# tenere-controller-rev-B.net
KiCad netlist of a schematic drawn in EAGLE
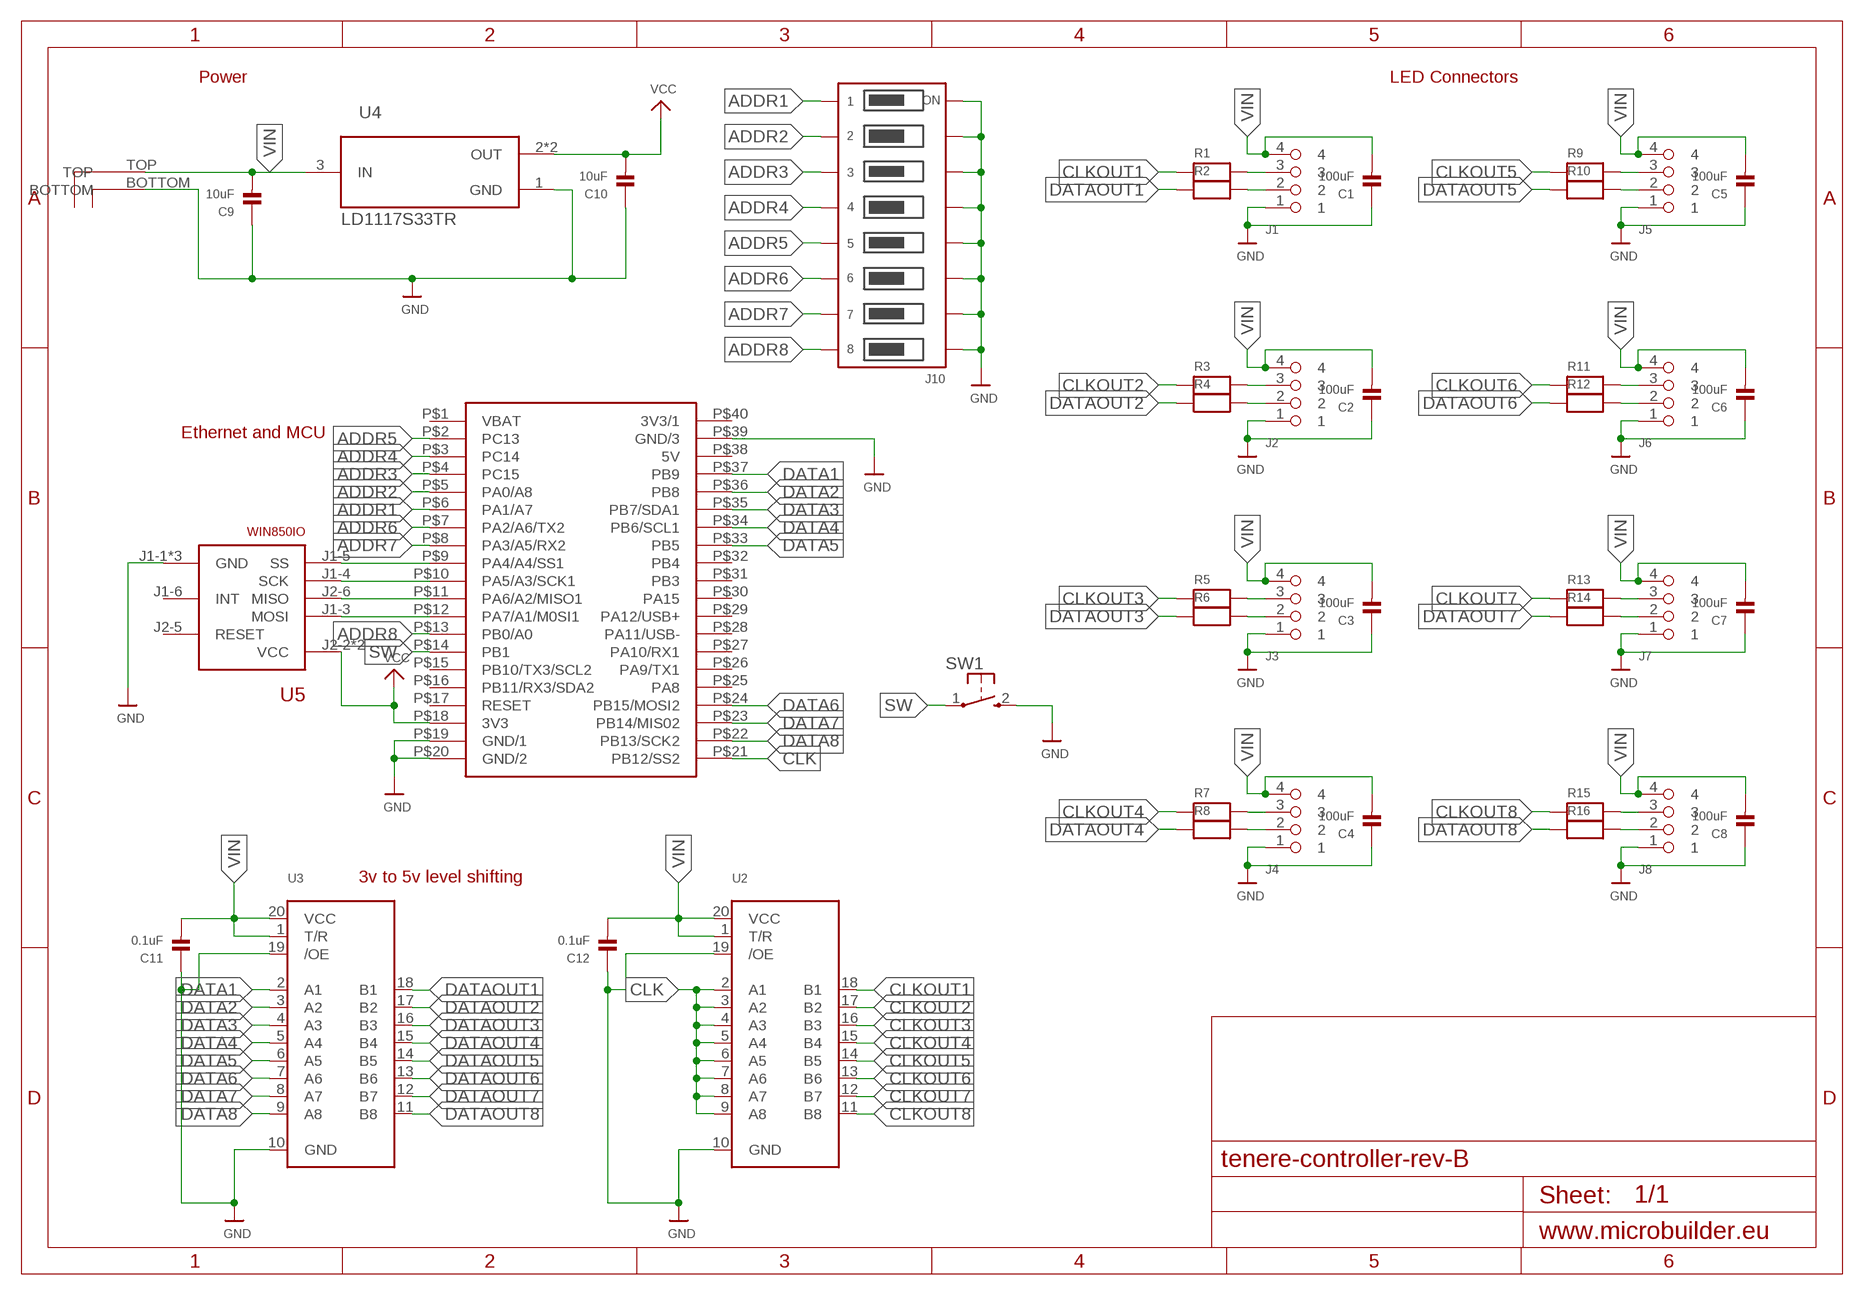
[diagram p0: schematic, sheet 1]

(export (version "E")
  (design (tool "Eeschema 10.0.6"))
  (components
    (comp (ref "C1")
      (value "100uF")
      (footprint "eagle-import:1206")
      (libsource (lib "eagle-import") (part "CAP_CERAMIC1206"))
    )
    (comp (ref "C2")
      (value "100uF")
      (footprint "eagle-import:1206")
      (libsource (lib "eagle-import") (part "CAP_CERAMIC1206"))
    )
    (comp (ref "C3")
      (value "100uF")
      (footprint "eagle-import:1206")
      (libsource (lib "eagle-import") (part "CAP_CERAMIC1206"))
    )
    (comp (ref "C4")
      (value "100uF")
      (footprint "eagle-import:1206")
      (libsource (lib "eagle-import") (part "CAP_CERAMIC1206"))
    )
    (comp (ref "C5")
      (value "100uF")
      (footprint "eagle-import:1206")
      (libsource (lib "eagle-import") (part "CAP_CERAMIC1206"))
    )
    (comp (ref "C6")
      (value "100uF")
      (footprint "eagle-import:1206")
      (libsource (lib "eagle-import") (part "CAP_CERAMIC1206"))
    )
    (comp (ref "C7")
      (value "100uF")
      (footprint "eagle-import:1206")
      (libsource (lib "eagle-import") (part "CAP_CERAMIC1206"))
    )
    (comp (ref "C8")
      (value "100uF")
      (footprint "eagle-import:1206")
      (libsource (lib "eagle-import") (part "CAP_CERAMIC1206"))
    )
    (comp (ref "C9")
      (value "10uF")
      (footprint "eagle-import:0603")
      (libsource (lib "eagle-import") (part "CAP_CERAMIC0603"))
    )
    (comp (ref "C10")
      (value "10uF")
      (footprint "eagle-import:0603")
      (libsource (lib "eagle-import") (part "CAP_CERAMIC0603"))
    )
    (comp (ref "C11")
      (value "0.1uF")
      (footprint "eagle-import:0603")
      (libsource (lib "eagle-import") (part "CAP_CERAMIC0603"))
    )
    (comp (ref "C12")
      (value "0.1uF")
      (footprint "eagle-import:0603")
      (libsource (lib "eagle-import") (part "CAP_CERAMIC0603"))
    )
    (comp (ref "J1")
      (value "MICROFIT3")
      (footprint "eagle-import:43650-0400")
      (libsource (lib "eagle-import") (part "MICROFIT3"))
    )
    (comp (ref "J2")
      (value "MICROFIT3")
      (footprint "eagle-import:43650-0400")
      (libsource (lib "eagle-import") (part "MICROFIT3"))
    )
    (comp (ref "J3")
      (value "MICROFIT3")
      (footprint "eagle-import:43650-0400")
      (libsource (lib "eagle-import") (part "MICROFIT3"))
    )
    (comp (ref "J4")
      (value "MICROFIT3")
      (footprint "eagle-import:43650-0400")
      (libsource (lib "eagle-import") (part "MICROFIT3"))
    )
    (comp (ref "J5")
      (value "MICROFIT3")
      (footprint "eagle-import:43650-0400")
      (libsource (lib "eagle-import") (part "MICROFIT3"))
    )
    (comp (ref "J6")
      (value "MICROFIT3")
      (footprint "eagle-import:43650-0400")
      (libsource (lib "eagle-import") (part "MICROFIT3"))
    )
    (comp (ref "J7")
      (value "MICROFIT3")
      (footprint "eagle-import:43650-0400")
      (libsource (lib "eagle-import") (part "MICROFIT3"))
    )
    (comp (ref "J8")
      (value "MICROFIT3")
      (footprint "eagle-import:43650-0400")
      (libsource (lib "eagle-import") (part "MICROFIT3"))
    )
    (comp (ref "J10")
      (value "DIP-SWITCH-8PIN")
      (footprint "eagle-import:BPA08B")
      (libsource (lib "eagle-import") (part "DIP-SWITCH-8PIN"))
    )
    (comp (ref "PWR")
      (value "POWERPOLE-2V")
      (footprint "eagle-import:POWERPOLE_STACKED")
      (libsource (lib "eagle-import") (part "POWERPOLE-2V"))
    )
    (comp (ref "R1")
      (value "RESISTOR0603")
      (footprint "eagle-import:0603")
      (libsource (lib "eagle-import") (part "RESISTOR0603"))
    )
    (comp (ref "R2")
      (value "RESISTOR0603")
      (footprint "eagle-import:0603")
      (libsource (lib "eagle-import") (part "RESISTOR0603"))
    )
    (comp (ref "R3")
      (value "RESISTOR0603")
      (footprint "eagle-import:0603")
      (libsource (lib "eagle-import") (part "RESISTOR0603"))
    )
    (comp (ref "R4")
      (value "RESISTOR0603")
      (footprint "eagle-import:0603")
      (libsource (lib "eagle-import") (part "RESISTOR0603"))
    )
    (comp (ref "R5")
      (value "RESISTOR0603")
      (footprint "eagle-import:0603")
      (libsource (lib "eagle-import") (part "RESISTOR0603"))
    )
    (comp (ref "R6")
      (value "RESISTOR0603")
      (footprint "eagle-import:0603")
      (libsource (lib "eagle-import") (part "RESISTOR0603"))
    )
    (comp (ref "R7")
      (value "RESISTOR0603")
      (footprint "eagle-import:0603")
      (libsource (lib "eagle-import") (part "RESISTOR0603"))
    )
    (comp (ref "R8")
      (value "RESISTOR0603")
      (footprint "eagle-import:0603")
      (libsource (lib "eagle-import") (part "RESISTOR0603"))
    )
    (comp (ref "R9")
      (value "RESISTOR0603")
      (footprint "eagle-import:0603")
      (libsource (lib "eagle-import") (part "RESISTOR0603"))
    )
    (comp (ref "R10")
      (value "RESISTOR0603")
      (footprint "eagle-import:0603")
      (libsource (lib "eagle-import") (part "RESISTOR0603"))
    )
    (comp (ref "R11")
      (value "RESISTOR0603")
      (footprint "eagle-import:0603")
      (libsource (lib "eagle-import") (part "RESISTOR0603"))
    )
    (comp (ref "R12")
      (value "RESISTOR0603")
      (footprint "eagle-import:0603")
      (libsource (lib "eagle-import") (part "RESISTOR0603"))
    )
    (comp (ref "R13")
      (value "RESISTOR0603")
      (footprint "eagle-import:0603")
      (libsource (lib "eagle-import") (part "RESISTOR0603"))
    )
    (comp (ref "R14")
      (value "RESISTOR0603")
      (footprint "eagle-import:0603")
      (libsource (lib "eagle-import") (part "RESISTOR0603"))
    )
    (comp (ref "R15")
      (value "RESISTOR0603")
      (footprint "eagle-import:0603")
      (libsource (lib "eagle-import") (part "RESISTOR0603"))
    )
    (comp (ref "R16")
      (value "RESISTOR0603")
      (footprint "eagle-import:0603")
      (libsource (lib "eagle-import") (part "RESISTOR0603"))
    )
    (comp (ref "SW1")
      (value "TACTILE-SWITCH-1825027")
      (footprint "eagle-import:1825027")
      (libsource (lib "eagle-import") (part "TACTILE-SWITCH-1825027"))
    )
    (comp (ref "U1")
      (value "BLUEPILL")
      (footprint "eagle-import:40-DIP-BLUE-PIL")
      (libsource (lib "eagle-import") (part "BLUEPILL"))
    )
    (comp (ref "U2")
      (value "74LCX245")
      (footprint "eagle-import:TSSOP20")
      (libsource (lib "eagle-import") (part "74LCX245"))
    )
    (comp (ref "U3")
      (value "74LCX245")
      (footprint "eagle-import:TSSOP20")
      (libsource (lib "eagle-import") (part "74LCX245"))
    )
    (comp (ref "U4")
      (value "LD1117S33TR")
      (footprint "eagle-import:LD1117S33TR_SOT230P700X180-4N")
      (fields (field (name "MANUFACTURER") "ST Microelectronics"))
      (libsource (lib "eagle-import") (part "LD1117S33TR"))
    )
    (comp (ref "U5")
      (value "WIN850IO")
      (footprint "eagle-import:WIZ850IO")
      (libsource (lib "eagle-import") (part "WIN850IO"))
    )
  )
  (nets
    (net (code "1") (name "ADDR1") (class "Default")
      (node (ref "J10") (pin "1'") (pinfunction "1B_1'") (pintype "bidirectional"))
      (node (ref "U1") (pin "P$6") (pinfunction "PA1/A7_P$6") (pintype "bidirectional"))
    )
    (net (code "2") (name "ADDR2") (class "Default")
      (node (ref "J10") (pin "2'") (pinfunction "2B_2'") (pintype "bidirectional"))
      (node (ref "U1") (pin "P$5") (pinfunction "PA0/A8_P$5") (pintype "bidirectional"))
    )
    (net (code "3") (name "ADDR3") (class "Default")
      (node (ref "J10") (pin "3'") (pinfunction "3B_3'") (pintype "bidirectional"))
      (node (ref "U1") (pin "P$4") (pinfunction "PC15_P$4") (pintype "bidirectional"))
    )
    (net (code "4") (name "ADDR4") (class "Default")
      (node (ref "J10") (pin "4'") (pinfunction "4B_4'") (pintype "bidirectional"))
      (node (ref "U1") (pin "P$3") (pinfunction "PC14_P$3") (pintype "bidirectional"))
    )
    (net (code "5") (name "ADDR5") (class "Default")
      (node (ref "J10") (pin "5'") (pinfunction "5B_5'") (pintype "bidirectional"))
      (node (ref "U1") (pin "P$2") (pinfunction "PC13_P$2") (pintype "bidirectional"))
    )
    (net (code "6") (name "ADDR6") (class "Default")
      (node (ref "J10") (pin "6'") (pinfunction "6B_6'") (pintype "bidirectional"))
      (node (ref "U1") (pin "P$7") (pinfunction "PA2/A6/TX2_P$7") (pintype "bidirectional"))
    )
    (net (code "7") (name "ADDR7") (class "Default")
      (node (ref "J10") (pin "7'") (pinfunction "7B_7'") (pintype "bidirectional"))
      (node (ref "U1") (pin "P$8") (pinfunction "PA3/A5/RX2_P$8") (pintype "bidirectional"))
    )
    (net (code "8") (name "ADDR8") (class "Default")
      (node (ref "J10") (pin "8'") (pinfunction "8B_8'") (pintype "bidirectional"))
      (node (ref "U1") (pin "P$13") (pinfunction "PB0/A0_P$13") (pintype "bidirectional"))
    )
    (net (code "9") (name "CLK") (class "Default")
      (node (ref "U1") (pin "P$21") (pinfunction "PB12/SS2_P$21") (pintype "bidirectional"))
      (node (ref "U2") (pin "2") (pinfunction "A1_2") (pintype "bidirectional"))
      (node (ref "U2") (pin "3") (pinfunction "A2_3") (pintype "bidirectional"))
      (node (ref "U2") (pin "4") (pinfunction "A3_4") (pintype "bidirectional"))
      (node (ref "U2") (pin "5") (pinfunction "A4_5") (pintype "bidirectional"))
      (node (ref "U2") (pin "6") (pinfunction "A5_6") (pintype "bidirectional"))
      (node (ref "U2") (pin "7") (pinfunction "A6_7") (pintype "bidirectional"))
      (node (ref "U2") (pin "8") (pinfunction "A7_8") (pintype "bidirectional"))
      (node (ref "U2") (pin "9") (pinfunction "A8_9") (pintype "bidirectional"))
    )
    (net (code "10") (name "CLKOUT1") (class "Default")
      (node (ref "R1") (pin "1") (pinfunction "1_1") (pintype "passive"))
      (node (ref "U2") (pin "18") (pinfunction "B1_18") (pintype "bidirectional"))
    )
    (net (code "11") (name "CLKOUT2") (class "Default")
      (node (ref "R3") (pin "1") (pinfunction "1_1") (pintype "passive"))
      (node (ref "U2") (pin "17") (pinfunction "B2_17") (pintype "bidirectional"))
    )
    (net (code "12") (name "CLKOUT3") (class "Default")
      (node (ref "R5") (pin "1") (pinfunction "1_1") (pintype "passive"))
      (node (ref "U2") (pin "16") (pinfunction "B3_16") (pintype "bidirectional"))
    )
    (net (code "13") (name "CLKOUT4") (class "Default")
      (node (ref "R7") (pin "1") (pinfunction "1_1") (pintype "passive"))
      (node (ref "U2") (pin "15") (pinfunction "B4_15") (pintype "bidirectional"))
    )
    (net (code "14") (name "CLKOUT5") (class "Default")
      (node (ref "R9") (pin "1") (pinfunction "1_1") (pintype "passive"))
      (node (ref "U2") (pin "14") (pinfunction "B5_14") (pintype "bidirectional"))
    )
    (net (code "15") (name "CLKOUT6") (class "Default")
      (node (ref "R11") (pin "1") (pinfunction "1_1") (pintype "passive"))
      (node (ref "U2") (pin "13") (pinfunction "B6_13") (pintype "bidirectional"))
    )
    (net (code "16") (name "CLKOUT7") (class "Default")
      (node (ref "R13") (pin "1") (pinfunction "1_1") (pintype "passive"))
      (node (ref "U2") (pin "12") (pinfunction "B7_12") (pintype "bidirectional"))
    )
    (net (code "17") (name "CLKOUT8") (class "Default")
      (node (ref "R15") (pin "1") (pinfunction "1_1") (pintype "passive"))
      (node (ref "U2") (pin "11") (pinfunction "B8_11") (pintype "bidirectional"))
    )
    (net (code "18") (name "DATA1") (class "Default")
      (node (ref "U1") (pin "P$37") (pinfunction "PB9_P$37") (pintype "bidirectional"))
      (node (ref "U3") (pin "2") (pinfunction "A1_2") (pintype "bidirectional"))
    )
    (net (code "19") (name "DATA2") (class "Default")
      (node (ref "U1") (pin "P$36") (pinfunction "PB8_P$36") (pintype "bidirectional"))
      (node (ref "U3") (pin "3") (pinfunction "A2_3") (pintype "bidirectional"))
    )
    (net (code "20") (name "DATA3") (class "Default")
      (node (ref "U1") (pin "P$35") (pinfunction "PB7/SDA1_P$35") (pintype "bidirectional"))
      (node (ref "U3") (pin "4") (pinfunction "A3_4") (pintype "bidirectional"))
    )
    (net (code "21") (name "DATA4") (class "Default")
      (node (ref "U1") (pin "P$34") (pinfunction "PB6/SCL1_P$34") (pintype "bidirectional"))
      (node (ref "U3") (pin "5") (pinfunction "A4_5") (pintype "bidirectional"))
    )
    (net (code "22") (name "DATA5") (class "Default")
      (node (ref "U1") (pin "P$33") (pinfunction "PB5_P$33") (pintype "bidirectional"))
      (node (ref "U3") (pin "6") (pinfunction "A5_6") (pintype "bidirectional"))
    )
    (net (code "23") (name "DATA6") (class "Default")
      (node (ref "U1") (pin "P$24") (pinfunction "PB15/MOSI2_P$24") (pintype "bidirectional"))
      (node (ref "U3") (pin "7") (pinfunction "A6_7") (pintype "bidirectional"))
    )
    (net (code "24") (name "DATA7") (class "Default")
      (node (ref "U1") (pin "P$23") (pinfunction "PB14/MIS02_P$23") (pintype "bidirectional"))
      (node (ref "U3") (pin "8") (pinfunction "A7_8") (pintype "bidirectional"))
    )
    (net (code "25") (name "DATA8") (class "Default")
      (node (ref "U1") (pin "P$22") (pinfunction "PB13/SCK2_P$22") (pintype "bidirectional"))
      (node (ref "U3") (pin "9") (pinfunction "A8_9") (pintype "bidirectional"))
    )
    (net (code "26") (name "DATAOUT1") (class "Default")
      (node (ref "R2") (pin "1") (pinfunction "1_1") (pintype "passive"))
      (node (ref "U3") (pin "18") (pinfunction "B1_18") (pintype "bidirectional"))
    )
    (net (code "27") (name "DATAOUT2") (class "Default")
      (node (ref "R4") (pin "1") (pinfunction "1_1") (pintype "passive"))
      (node (ref "U3") (pin "17") (pinfunction "B2_17") (pintype "bidirectional"))
    )
    (net (code "28") (name "DATAOUT3") (class "Default")
      (node (ref "R6") (pin "1") (pinfunction "1_1") (pintype "passive"))
      (node (ref "U3") (pin "16") (pinfunction "B3_16") (pintype "bidirectional"))
    )
    (net (code "29") (name "DATAOUT4") (class "Default")
      (node (ref "R8") (pin "1") (pinfunction "1_1") (pintype "passive"))
      (node (ref "U3") (pin "15") (pinfunction "B4_15") (pintype "bidirectional"))
    )
    (net (code "30") (name "DATAOUT5") (class "Default")
      (node (ref "R10") (pin "1") (pinfunction "1_1") (pintype "passive"))
      (node (ref "U3") (pin "14") (pinfunction "B5_14") (pintype "bidirectional"))
    )
    (net (code "31") (name "DATAOUT6") (class "Default")
      (node (ref "R12") (pin "1") (pinfunction "1_1") (pintype "passive"))
      (node (ref "U3") (pin "13") (pinfunction "B6_13") (pintype "bidirectional"))
    )
    (net (code "32") (name "DATAOUT7") (class "Default")
      (node (ref "R14") (pin "1") (pinfunction "1_1") (pintype "passive"))
      (node (ref "U3") (pin "12") (pinfunction "B7_12") (pintype "bidirectional"))
    )
    (net (code "33") (name "DATAOUT8") (class "Default")
      (node (ref "R16") (pin "1") (pinfunction "1_1") (pintype "passive"))
      (node (ref "U3") (pin "11") (pinfunction "B8_11") (pintype "bidirectional"))
    )
    (net (code "34") (name "GND") (class "Default")
      (node (ref "C1") (pin "1") (pinfunction "P$1_1") (pintype "passive"))
      (node (ref "C10") (pin "1") (pinfunction "P$1_1") (pintype "passive"))
      (node (ref "C11") (pin "1") (pinfunction "P$1_1") (pintype "passive"))
      (node (ref "C12") (pin "1") (pinfunction "P$1_1") (pintype "passive"))
      (node (ref "C2") (pin "1") (pinfunction "P$1_1") (pintype "passive"))
      (node (ref "C3") (pin "1") (pinfunction "P$1_1") (pintype "passive"))
      (node (ref "C4") (pin "1") (pinfunction "P$1_1") (pintype "passive"))
      (node (ref "C5") (pin "1") (pinfunction "P$1_1") (pintype "passive"))
      (node (ref "C6") (pin "1") (pinfunction "P$1_1") (pintype "passive"))
      (node (ref "C7") (pin "1") (pinfunction "P$1_1") (pintype "passive"))
      (node (ref "C8") (pin "1") (pinfunction "P$1_1") (pintype "passive"))
      (node (ref "C9") (pin "1") (pinfunction "P$1_1") (pintype "passive"))
      (node (ref "J1") (pin "1") (pinfunction "1_1") (pintype "bidirectional"))
      (node (ref "J10") (pin "1") (pinfunction "1A_1") (pintype "bidirectional"))
      (node (ref "J10") (pin "2") (pinfunction "2A_2") (pintype "bidirectional"))
      (node (ref "J10") (pin "3") (pinfunction "3A_3") (pintype "bidirectional"))
      (node (ref "J10") (pin "4") (pinfunction "4A_4") (pintype "bidirectional"))
      (node (ref "J10") (pin "5") (pinfunction "5A_5") (pintype "bidirectional"))
      (node (ref "J10") (pin "6") (pinfunction "6A_6") (pintype "bidirectional"))
      (node (ref "J10") (pin "7") (pinfunction "7A_7") (pintype "bidirectional"))
      (node (ref "J10") (pin "8") (pinfunction "8A_8") (pintype "bidirectional"))
      (node (ref "J2") (pin "1") (pinfunction "1_1") (pintype "bidirectional"))
      (node (ref "J3") (pin "1") (pinfunction "1_1") (pintype "bidirectional"))
      (node (ref "J4") (pin "1") (pinfunction "1_1") (pintype "bidirectional"))
      (node (ref "J5") (pin "1") (pinfunction "1_1") (pintype "bidirectional"))
      (node (ref "J6") (pin "1") (pinfunction "1_1") (pintype "bidirectional"))
      (node (ref "J7") (pin "1") (pinfunction "1_1") (pintype "bidirectional"))
      (node (ref "J8") (pin "1") (pinfunction "1_1") (pintype "bidirectional"))
      (node (ref "PWR") (pin "BOTTOM") (pinfunction "BOTTOM_BOTTOM") (pintype "bidirectional"))
      (node (ref "SW1") (pin "2") (pinfunction "3_2") (pintype "passive"))
      (node (ref "U1") (pin "P$19") (pinfunction "GND/1_P$19") (pintype "bidirectional"))
      (node (ref "U1") (pin "P$20") (pinfunction "GND/2_P$20") (pintype "bidirectional"))
      (node (ref "U1") (pin "P$39") (pinfunction "GND/3_P$39") (pintype "bidirectional"))
      (node (ref "U2") (pin "10") (pinfunction "GND_10") (pintype "bidirectional"))
      (node (ref "U2") (pin "19") (pinfunction "/OE_19") (pintype "bidirectional"))
      (node (ref "U3") (pin "10") (pinfunction "GND_10") (pintype "bidirectional"))
      (node (ref "U3") (pin "19") (pinfunction "/OE_19") (pintype "bidirectional"))
      (node (ref "U4") (pin "1") (pinfunction "GND_1") (pintype "power_in"))
      (node (ref "U5") (pin "J1-1") (pinfunction "GND_J1-1") (pintype "bidirectional"))
      (node (ref "U5") (pin "J1-2") (pinfunction "GND_J1-2") (pintype "bidirectional"))
      (node (ref "U5") (pin "J2-1") (pinfunction "GND_J2-1") (pintype "bidirectional"))
    )
    (net (code "35") (name "Net-(J1-Pad2)") (class "Default")
      (node (ref "J1") (pin "2") (pinfunction "2_2") (pintype "bidirectional"))
      (node (ref "R2") (pin "2") (pinfunction "2_2") (pintype "passive"))
    )
    (net (code "36") (name "Net-(J1-Pad3)") (class "Default")
      (node (ref "J1") (pin "3") (pinfunction "3_3") (pintype "bidirectional"))
      (node (ref "R1") (pin "2") (pinfunction "2_2") (pintype "passive"))
    )
    (net (code "37") (name "Net-(J2-Pad2)") (class "Default")
      (node (ref "J2") (pin "2") (pinfunction "2_2") (pintype "bidirectional"))
      (node (ref "R4") (pin "2") (pinfunction "2_2") (pintype "passive"))
    )
    (net (code "38") (name "Net-(J2-Pad3)") (class "Default")
      (node (ref "J2") (pin "3") (pinfunction "3_3") (pintype "bidirectional"))
      (node (ref "R3") (pin "2") (pinfunction "2_2") (pintype "passive"))
    )
    (net (code "39") (name "Net-(J3-Pad2)") (class "Default")
      (node (ref "J3") (pin "2") (pinfunction "2_2") (pintype "bidirectional"))
      (node (ref "R6") (pin "2") (pinfunction "2_2") (pintype "passive"))
    )
    (net (code "40") (name "Net-(J3-Pad3)") (class "Default")
      (node (ref "J3") (pin "3") (pinfunction "3_3") (pintype "bidirectional"))
      (node (ref "R5") (pin "2") (pinfunction "2_2") (pintype "passive"))
    )
    (net (code "41") (name "Net-(J4-Pad2)") (class "Default")
      (node (ref "J4") (pin "2") (pinfunction "2_2") (pintype "bidirectional"))
      (node (ref "R8") (pin "2") (pinfunction "2_2") (pintype "passive"))
    )
    (net (code "42") (name "Net-(J4-Pad3)") (class "Default")
      (node (ref "J4") (pin "3") (pinfunction "3_3") (pintype "bidirectional"))
      (node (ref "R7") (pin "2") (pinfunction "2_2") (pintype "passive"))
    )
    (net (code "43") (name "Net-(J5-Pad2)") (class "Default")
      (node (ref "J5") (pin "2") (pinfunction "2_2") (pintype "bidirectional"))
      (node (ref "R10") (pin "2") (pinfunction "2_2") (pintype "passive"))
    )
    (net (code "44") (name "Net-(J5-Pad3)") (class "Default")
      (node (ref "J5") (pin "3") (pinfunction "3_3") (pintype "bidirectional"))
      (node (ref "R9") (pin "2") (pinfunction "2_2") (pintype "passive"))
    )
    (net (code "45") (name "Net-(J6-Pad2)") (class "Default")
      (node (ref "J6") (pin "2") (pinfunction "2_2") (pintype "bidirectional"))
      (node (ref "R12") (pin "2") (pinfunction "2_2") (pintype "passive"))
    )
    (net (code "46") (name "Net-(J6-Pad3)") (class "Default")
      (node (ref "J6") (pin "3") (pinfunction "3_3") (pintype "bidirectional"))
      (node (ref "R11") (pin "2") (pinfunction "2_2") (pintype "passive"))
    )
    (net (code "47") (name "Net-(J7-Pad2)") (class "Default")
      (node (ref "J7") (pin "2") (pinfunction "2_2") (pintype "bidirectional"))
      (node (ref "R14") (pin "2") (pinfunction "2_2") (pintype "passive"))
    )
    (net (code "48") (name "Net-(J7-Pad3)") (class "Default")
      (node (ref "J7") (pin "3") (pinfunction "3_3") (pintype "bidirectional"))
      (node (ref "R13") (pin "2") (pinfunction "2_2") (pintype "passive"))
    )
    (net (code "49") (name "Net-(J8-Pad2)") (class "Default")
      (node (ref "J8") (pin "2") (pinfunction "2_2") (pintype "bidirectional"))
      (node (ref "R16") (pin "2") (pinfunction "2_2") (pintype "passive"))
    )
    (net (code "50") (name "Net-(J8-Pad3)") (class "Default")
      (node (ref "J8") (pin "3") (pinfunction "3_3") (pintype "bidirectional"))
      (node (ref "R15") (pin "2") (pinfunction "2_2") (pintype "passive"))
    )
    (net (code "51") (name "Net-(U1-PA4{slash}A4{slash}SS1)") (class "Default")
      (node (ref "U1") (pin "P$9") (pinfunction "PA4/A4/SS1_P$9") (pintype "bidirectional"))
      (node (ref "U5") (pin "J1-5") (pinfunction "SS_J1-5") (pintype "bidirectional"))
    )
    (net (code "52") (name "Net-(U1-PA5{slash}A3{slash}SCK1)") (class "Default")
      (node (ref "U1") (pin "P$10") (pinfunction "PA5/A3/SCK1_P$10") (pintype "bidirectional"))
      (node (ref "U5") (pin "J1-4") (pinfunction "SCK_J1-4") (pintype "bidirectional"))
    )
    (net (code "53") (name "Net-(U1-PA6{slash}A2{slash}MISO1)") (class "Default")
      (node (ref "U1") (pin "P$11") (pinfunction "PA6/A2/MISO1_P$11") (pintype "bidirectional"))
      (node (ref "U5") (pin "J2-6") (pinfunction "MISO_J2-6") (pintype "bidirectional"))
    )
    (net (code "54") (name "Net-(U1-PA7{slash}A1{slash}M0SI1)") (class "Default")
      (node (ref "U1") (pin "P$12") (pinfunction "PA7/A1/M0SI1_P$12") (pintype "bidirectional"))
      (node (ref "U5") (pin "J1-3") (pinfunction "MOSI_J1-3") (pintype "bidirectional"))
    )
    (net (code "55") (name "SW") (class "Default")
      (node (ref "SW1") (pin "1") (pinfunction "1_1") (pintype "passive"))
      (node (ref "U1") (pin "P$14") (pinfunction "PB1_P$14") (pintype "bidirectional"))
    )
    (net (code "56") (name "VCC") (class "Default")
      (node (ref "C10") (pin "2") (pinfunction "P$2_2") (pintype "passive"))
      (node (ref "U1") (pin "P$18") (pinfunction "3V3_P$18") (pintype "bidirectional"))
      (node (ref "U4") (pin "2") (pinfunction "OUT_2") (pintype "output"))
      (node (ref "U4") (pin "4") (pinfunction "OUT_4") (pintype "output"))
      (node (ref "U5") (pin "J2-2") (pinfunction "VCC_J2-2") (pintype "bidirectional"))
      (node (ref "U5") (pin "J2-3") (pinfunction "VCC_J2-3") (pintype "bidirectional"))
    )
    (net (code "57") (name "VIN") (class "Default")
      (node (ref "C1") (pin "2") (pinfunction "P$2_2") (pintype "passive"))
      (node (ref "C11") (pin "2") (pinfunction "P$2_2") (pintype "passive"))
      (node (ref "C12") (pin "2") (pinfunction "P$2_2") (pintype "passive"))
      (node (ref "C2") (pin "2") (pinfunction "P$2_2") (pintype "passive"))
      (node (ref "C3") (pin "2") (pinfunction "P$2_2") (pintype "passive"))
      (node (ref "C4") (pin "2") (pinfunction "P$2_2") (pintype "passive"))
      (node (ref "C5") (pin "2") (pinfunction "P$2_2") (pintype "passive"))
      (node (ref "C6") (pin "2") (pinfunction "P$2_2") (pintype "passive"))
      (node (ref "C7") (pin "2") (pinfunction "P$2_2") (pintype "passive"))
      (node (ref "C8") (pin "2") (pinfunction "P$2_2") (pintype "passive"))
      (node (ref "C9") (pin "2") (pinfunction "P$2_2") (pintype "passive"))
      (node (ref "J1") (pin "4") (pinfunction "4_4") (pintype "bidirectional"))
      (node (ref "J2") (pin "4") (pinfunction "4_4") (pintype "bidirectional"))
      (node (ref "J3") (pin "4") (pinfunction "4_4") (pintype "bidirectional"))
      (node (ref "J4") (pin "4") (pinfunction "4_4") (pintype "bidirectional"))
      (node (ref "J5") (pin "4") (pinfunction "4_4") (pintype "bidirectional"))
      (node (ref "J6") (pin "4") (pinfunction "4_4") (pintype "bidirectional"))
      (node (ref "J7") (pin "4") (pinfunction "4_4") (pintype "bidirectional"))
      (node (ref "J8") (pin "4") (pinfunction "4_4") (pintype "bidirectional"))
      (node (ref "PWR") (pin "TOP") (pinfunction "TOP_TOP") (pintype "bidirectional"))
      (node (ref "U2") (pin "1") (pinfunction "T/R_1") (pintype "bidirectional"))
      (node (ref "U2") (pin "20") (pinfunction "VCC_20") (pintype "bidirectional"))
      (node (ref "U3") (pin "1") (pinfunction "T/R_1") (pintype "bidirectional"))
      (node (ref "U3") (pin "20") (pinfunction "VCC_20") (pintype "bidirectional"))
      (node (ref "U4") (pin "3") (pinfunction "IN_3") (pintype "input"))
    )
    (net (code "58") (name "unconnected-(U1-3V3{slash}1-PadP$40)") (class "Default")
      (node (ref "U1") (pin "P$40") (pinfunction "3V3/1_P$40") (pintype "bidirectional"))
    )
    (net (code "59") (name "unconnected-(U1-5V-PadP$38)") (class "Default")
      (node (ref "U1") (pin "P$38") (pinfunction "5V_P$38") (pintype "bidirectional"))
    )
    (net (code "60") (name "unconnected-(U1-PA8-PadP$25)") (class "Default")
      (node (ref "U1") (pin "P$25") (pinfunction "PA8_P$25") (pintype "bidirectional"))
    )
    (net (code "61") (name "unconnected-(U1-PA9{slash}TX1-PadP$26)") (class "Default")
      (node (ref "U1") (pin "P$26") (pinfunction "PA9/TX1_P$26") (pintype "bidirectional"))
    )
    (net (code "62") (name "unconnected-(U1-PA10{slash}RX1-PadP$27)") (class "Default")
      (node (ref "U1") (pin "P$27") (pinfunction "PA10/RX1_P$27") (pintype "bidirectional"))
    )
    (net (code "63") (name "unconnected-(U1-PA11{slash}USB--PadP$28)") (class "Default")
      (node (ref "U1") (pin "P$28") (pinfunction "PA11/USB-_P$28") (pintype "bidirectional"))
    )
    (net (code "64") (name "unconnected-(U1-PA12{slash}USB+-PadP$29)") (class "Default")
      (node (ref "U1") (pin "P$29") (pinfunction "PA12/USB+_P$29") (pintype "bidirectional"))
    )
    (net (code "65") (name "unconnected-(U1-PA15-PadP$30)") (class "Default")
      (node (ref "U1") (pin "P$30") (pinfunction "PA15_P$30") (pintype "bidirectional"))
    )
    (net (code "66") (name "unconnected-(U1-PB3-PadP$31)") (class "Default")
      (node (ref "U1") (pin "P$31") (pinfunction "PB3_P$31") (pintype "bidirectional"))
    )
    (net (code "67") (name "unconnected-(U1-PB4-PadP$32)") (class "Default")
      (node (ref "U1") (pin "P$32") (pinfunction "PB4_P$32") (pintype "bidirectional"))
    )
    (net (code "68") (name "unconnected-(U1-PB10{slash}TX3{slash}SCL2-PadP$15)") (class "Default")
      (node (ref "U1") (pin "P$15") (pinfunction "PB10/TX3/SCL2_P$15") (pintype "bidirectional"))
    )
    (net (code "69") (name "unconnected-(U1-PB11{slash}RX3{slash}SDA2-PadP$16)") (class "Default")
      (node (ref "U1") (pin "P$16") (pinfunction "PB11/RX3/SDA2_P$16") (pintype "bidirectional"))
    )
    (net (code "70") (name "unconnected-(U1-RESET-PadP$17)") (class "Default")
      (node (ref "U1") (pin "P$17") (pinfunction "RESET_P$17") (pintype "bidirectional"))
    )
    (net (code "71") (name "unconnected-(U1-VBAT-PadP$1)") (class "Default")
      (node (ref "U1") (pin "P$1") (pinfunction "VBAT_P$1") (pintype "bidirectional"))
    )
    (net (code "72") (name "unconnected-(U5-INT-PadJ1-6)") (class "Default")
      (node (ref "U5") (pin "J1-6") (pinfunction "INT_J1-6") (pintype "bidirectional"))
    )
    (net (code "73") (name "unconnected-(U5-RESET-PadJ2-5)") (class "Default")
      (node (ref "U5") (pin "J2-5") (pinfunction "RESET_J2-5") (pintype "bidirectional"))
    )
  )
)
